# ISL.net
KiCad netlist of a schematic drawn in Altium Designer
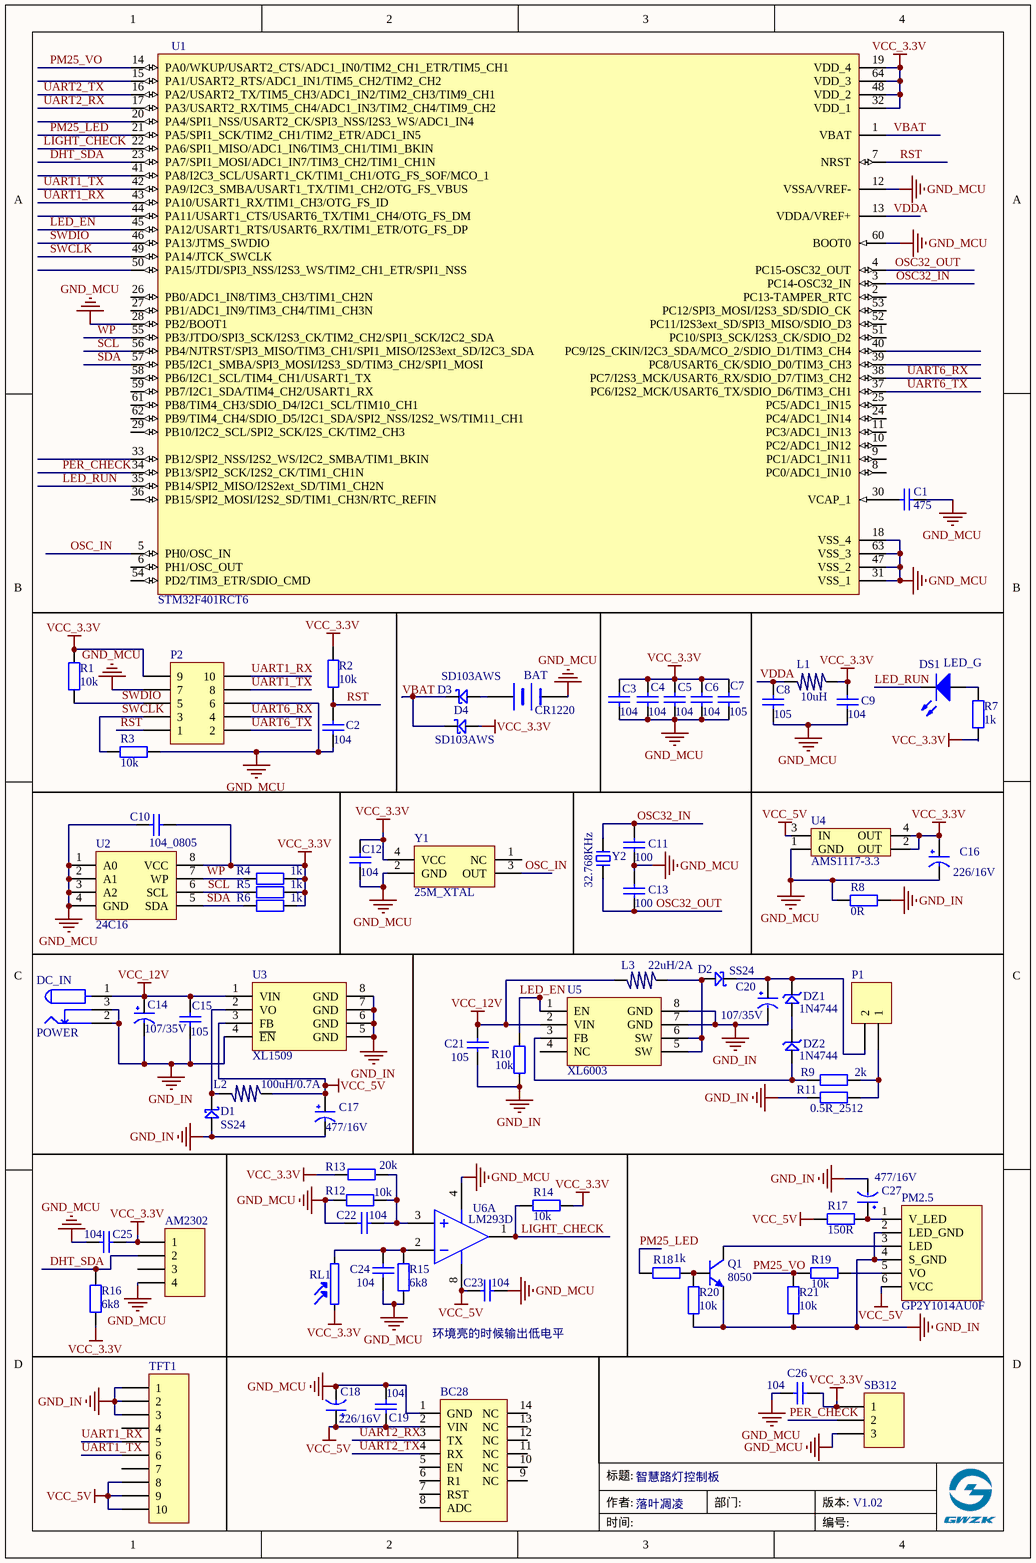
[diagram p0: ISL.SchDoc]

(export (version "E")
  (design (tool "Eeschema 10.0.6"))
  (components
    (comp (ref "AM2302")
      (value "Header 4")
      (footprint "AM2302(DHT11)")
      (description "Header, 4-Pin")
      (fields (field (name "PUBLISHER") "Altium Limited"))
      (libsource (lib "Miscellaneous Connectors") (part "Header 4"))
    )
    (comp (ref "BAT") (value "CR1220") (footprint "CR1220_B") (libsource (lib "*") (part "BATTERY")))
    (comp (ref "BC28") (value "BC28") (footprint "BC28-安联德") (libsource (lib "SCHLIB_LJF") (part "BC28")))
    (comp (ref "C1")
      (value "475")
      (footprint "C 0805")
      (description "Capacitor")
      (fields (field (name "PUBLISHER") "Altium Limited"))
      (libsource (lib "Miscellaneous Devices") (part "Cap"))
    )
    (comp (ref "C2")
      (value "104")
      (footprint "C 0805")
      (description "Capacitor")
      (fields (field (name "PUBLISHER") "Altium Limited"))
      (libsource (lib "Miscellaneous Devices") (part "Cap"))
    )
    (comp (ref "C3")
      (value "104")
      (footprint "C 0805")
      (description "Capacitor")
      (fields (field (name "PUBLISHER") "Altium Limited"))
      (libsource (lib "Miscellaneous Devices") (part "Cap"))
    )
    (comp (ref "C4")
      (value "104")
      (footprint "C 0805")
      (description "Capacitor")
      (fields (field (name "PUBLISHER") "Altium Limited"))
      (libsource (lib "Miscellaneous Devices") (part "Cap"))
    )
    (comp (ref "C5")
      (value "104")
      (footprint "C 0805")
      (description "Capacitor")
      (fields (field (name "PUBLISHER") "Altium Limited"))
      (libsource (lib "Miscellaneous Devices") (part "Cap"))
    )
    (comp (ref "C6")
      (value "104")
      (footprint "C 0805")
      (description "Capacitor")
      (fields (field (name "PUBLISHER") "Altium Limited"))
      (libsource (lib "Miscellaneous Devices") (part "Cap"))
    )
    (comp (ref "C7")
      (value "105")
      (footprint "C 0805")
      (description "Capacitor")
      (fields (field (name "PUBLISHER") "Altium Limited"))
      (libsource (lib "Miscellaneous Devices") (part "Cap"))
    )
    (comp (ref "C8")
      (value "105")
      (footprint "C 0805")
      (description "Capacitor")
      (fields (field (name "PUBLISHER") "Altium Limited"))
      (libsource (lib "Miscellaneous Devices") (part "Cap"))
    )
    (comp (ref "C9")
      (value "104")
      (footprint "C 0805")
      (description "Capacitor")
      (fields (field (name "PUBLISHER") "Altium Limited"))
      (libsource (lib "Miscellaneous Devices") (part "Cap"))
    )
    (comp (ref "C10")
      (value "104_0805")
      (footprint "C 0805")
      (description "Capacitor")
      (fields (field (name "PUBLISHER") "Altium Limited"))
      (libsource (lib "Miscellaneous Devices") (part "Cap"))
    )
    (comp (ref "C11")
      (value "100")
      (footprint "C 0805")
      (description "Capacitor")
      (fields (field (name "PUBLISHER") "Altium Limited"))
      (libsource (lib "Miscellaneous Devices") (part "Cap"))
    )
    (comp (ref "C12")
      (value "104")
      (footprint "C 0805")
      (description "Capacitor")
      (fields (field (name "PUBLISHER") "Altium Limited"))
      (libsource (lib "Miscellaneous Devices") (part "Cap"))
    )
    (comp (ref "C13")
      (value "100")
      (footprint "C 0805")
      (description "Capacitor")
      (fields (field (name "PUBLISHER") "Altium Limited"))
      (libsource (lib "Miscellaneous Devices") (part "Cap"))
    )
    (comp (ref "C14") (value "107/35V") (footprint "CAP 2.5*6.3*11.2") (libsource (lib "原理图库") (part "CAP")))
    (comp (ref "C15")
      (value "105")
      (footprint "C 0805")
      (description "Capacitor")
      (fields (field (name "PUBLISHER") "Altium Limited"))
      (libsource (lib "Miscellaneous Devices") (part "Cap"))
    )
    (comp (ref "C16") (value "226/16V") (footprint "CD B(3528)") (libsource (lib "原理图库") (part "CAP")))
    (comp (ref "C17") (value "477/16V") (footprint "CAP 3.5*8*11.5") (libsource (lib "原理图库") (part "CAP")))
    (comp (ref "C18") (value "226/16V") (footprint "CD B(3528)") (libsource (lib "") (part "CAP_1")))
    (comp (ref "C19")
      (value "104")
      (footprint "C 0805")
      (description "Capacitor")
      (fields (field (name "PUBLISHER") "Altium Limited"))
      (libsource (lib "Miscellaneous Devices") (part "Cap"))
    )
    (comp (ref "C20") (value "107/35V") (footprint "CAP 2.5*6.3*11.2") (libsource (lib "原理图库") (part "CAP")))
    (comp (ref "C21")
      (value "105")
      (footprint "C 0805")
      (description "Capacitor")
      (fields (field (name "PUBLISHER") "Altium Limited"))
      (libsource (lib "Miscellaneous Devices") (part "Cap"))
    )
    (comp (ref "C22")
      (value "104")
      (footprint "C 0805")
      (description "Capacitor")
      (fields (field (name "PUBLISHER") "Altium Limited"))
      (libsource (lib "Miscellaneous Devices") (part "Cap"))
    )
    (comp (ref "C23")
      (value "104")
      (footprint "C 0805")
      (description "Capacitor")
      (fields (field (name "PUBLISHER") "Altium Limited"))
      (libsource (lib "Miscellaneous Devices") (part "Cap"))
    )
    (comp (ref "C24")
      (value "104")
      (footprint "C 0805")
      (description "Capacitor")
      (fields (field (name "PUBLISHER") "Altium Limited"))
      (libsource (lib "Miscellaneous Devices") (part "Cap"))
    )
    (comp (ref "C25")
      (value "104")
      (footprint "C 0805")
      (description "Capacitor")
      (fields (field (name "PUBLISHER") "Altium Limited"))
      (libsource (lib "Miscellaneous Devices") (part "Cap"))
    )
    (comp (ref "C26")
      (value "104")
      (footprint "C 0805")
      (description "Capacitor")
      (fields (field (name "PUBLISHER") "Altium Limited"))
      (libsource (lib "Miscellaneous Devices") (part "Cap"))
    )
    (comp (ref "C27") (value "477/16V") (footprint "CAP 3.5*8*11.5") (libsource (lib "") (part "CAP_1")))
    (comp (ref "D1") (value "SS24") (footprint "SMA") (libsource (lib "原理图库") (part "D_SCHOTTYK")))
    (comp (ref "D2") (value "SS24") (footprint "SMA") (libsource (lib "原理图库") (part "D_SCHOTTYK")))
    (comp (ref "D3") (value "SD103AWS") (footprint "SOD-323") (libsource (lib "原理图库") (part "D_SCHOTTYK")))
    (comp (ref "D4") (value "SD103AWS") (footprint "SOD-323") (libsource (lib "原理图库") (part "D_SCHOTTYK")))
    (comp (ref "DC_IN") (value "POWER") (footprint "DC-005") (libsource (lib "原理图库") (part "POWER")))
    (comp (ref "DS1")
      (value "LED_G")
      (footprint "LED 0805")
      (description "Typical RED, GREEN, YELLOW, AMBER GaAs LED")
      (fields (field (name "PUBLISHER") "Altium Limited"))
      (libsource (lib "原理图库") (part "LED"))
    )
    (comp (ref "DZ1") (value "1N4744") (footprint "DO-41") (libsource (lib "原理图库") (part "D_ZENER")))
    (comp (ref "DZ2") (value "1N4744") (footprint "DO-41") (libsource (lib "原理图库") (part "D_ZENER")))
    (comp (ref "L1") (value "10uH") (footprint "L 0805") (libsource (lib "原理图库") (part "L")))
    (comp (ref "L2") (value "100uH/0.7A") (footprint "NR6045") (libsource (lib "原理图库") (part "L")))
    (comp (ref "L3") (value "22uH/2A") (footprint "NR6045") (libsource (lib "原理图库") (part "L")))
    (comp (ref "P1")
      (value "Header 2")
      (footprint "KF2EDGRM-X-2P")
      (description "Header, 2-Pin")
      (fields (field (name "PUBLISHER") "Altium Limited"))
      (libsource (lib "Miscellaneous Connectors") (part "Header 2"))
    )
    (comp (ref "P2")
      (value "Header 5X2")
      (footprint "HDR2.54-WI-2x5P")
      (description "Header, 5-Pin, Dual row")
      (fields (field (name "PUBLISHER") "Altium Limited"))
      (libsource (lib "Miscellaneous Connectors") (part "Header 5X2"))
    )
    (comp (ref "PM2.5")
      (value "GP2Y1014AU0F")
      (footprint "PH2.0-WS-6P")
      (libsource (lib "SCHLIB_LJF") (part "GP2Y1014AU0F"))
    )
    (comp (ref "Q1")
      (value "8050")
      (footprint "SOT23-3N")
      (description "NPN General Purpose Amplifier")
      (fields (field (name "PUBLISHER") "Altium Limited"))
      (libsource (lib "Miscellaneous Devices") (part "2N3904"))
    )
    (comp (ref "R1")
      (value "10k")
      (footprint "R 0805")
      (description "Resistor")
      (fields (field (name "PUBLISHER") "Altium Limited"))
      (libsource (lib "Miscellaneous Devices") (part "Res2"))
    )
    (comp (ref "R2")
      (value "10k")
      (footprint "R 0805")
      (description "Resistor")
      (fields (field (name "PUBLISHER") "Altium Limited"))
      (libsource (lib "Miscellaneous Devices") (part "Res2"))
    )
    (comp (ref "R3")
      (value "10k")
      (footprint "R 0805")
      (description "Resistor")
      (fields (field (name "PUBLISHER") "Altium Limited"))
      (libsource (lib "") (part "Res2_2"))
    )
    (comp (ref "R4")
      (value "1k")
      (footprint "R 0805")
      (description "Resistor")
      (fields (field (name "PUBLISHER") "Altium Limited"))
      (libsource (lib "") (part "Res2_2"))
    )
    (comp (ref "R5")
      (value "1k")
      (footprint "R 0805")
      (description "Resistor")
      (fields (field (name "PUBLISHER") "Altium Limited"))
      (libsource (lib "") (part "Res2_2"))
    )
    (comp (ref "R6")
      (value "1k")
      (footprint "R 0805")
      (description "Resistor")
      (fields (field (name "PUBLISHER") "Altium Limited"))
      (libsource (lib "") (part "Res2_2"))
    )
    (comp (ref "R7")
      (value "1k")
      (footprint "R 0805")
      (description "Resistor")
      (fields (field (name "PUBLISHER") "Altium Limited"))
      (libsource (lib "Miscellaneous Devices") (part "Res2"))
    )
    (comp (ref "R8")
      (value "0R")
      (footprint "R 0805")
      (description "Resistor")
      (fields (field (name "PUBLISHER") "Altium Limited"))
      (libsource (lib "") (part "Res2_3"))
    )
    (comp (ref "R9")
      (value "2k")
      (footprint "R 0805")
      (description "Resistor")
      (fields (field (name "PUBLISHER") "Altium Limited"))
      (libsource (lib "") (part "Res2_2"))
    )
    (comp (ref "R10")
      (value "10k")
      (footprint "R 0805")
      (description "Resistor")
      (fields (field (name "PUBLISHER") "Altium Limited"))
      (libsource (lib "") (part "Res2_1"))
    )
    (comp (ref "R11")
      (value "0.5R_2512")
      (footprint "R 2512")
      (description "Resistor")
      (fields (field (name "PUBLISHER") "Altium Limited"))
      (libsource (lib "") (part "Res2_2"))
    )
    (comp (ref "R12")
      (value "10k")
      (footprint "R 0805")
      (description "Resistor")
      (fields (field (name "PUBLISHER") "Altium Limited"))
      (libsource (lib "") (part "Res2_2"))
    )
    (comp (ref "R13")
      (value "20k")
      (footprint "R 0805")
      (description "Resistor")
      (fields (field (name "PUBLISHER") "Altium Limited"))
      (libsource (lib "") (part "Res2_3"))
    )
    (comp (ref "R14")
      (value "10k")
      (footprint "R 0805")
      (description "Resistor")
      (fields (field (name "PUBLISHER") "Altium Limited"))
      (libsource (lib "") (part "Res2_2"))
    )
    (comp (ref "R15")
      (value "6k8")
      (footprint "R 0805")
      (description "Resistor")
      (fields (field (name "PUBLISHER") "Altium Limited"))
      (libsource (lib "") (part "Res2_1"))
    )
    (comp (ref "R16")
      (value "6k8")
      (footprint "R 0805")
      (description "Resistor")
      (fields (field (name "PUBLISHER") "Altium Limited"))
      (libsource (lib "") (part "Res2_1"))
    )
    (comp (ref "R17")
      (value "150R")
      (footprint "R 0805")
      (description "Resistor")
      (fields (field (name "PUBLISHER") "Altium Limited"))
      (libsource (lib "") (part "Res2_2"))
    )
    (comp (ref "R18")
      (value "1k")
      (footprint "R 0805")
      (description "Resistor")
      (fields (field (name "PUBLISHER") "Altium Limited"))
      (libsource (lib "") (part "Res2_3"))
    )
    (comp (ref "R19")
      (value "10k")
      (footprint "R 0805")
      (description "Resistor")
      (fields (field (name "PUBLISHER") "Altium Limited"))
      (libsource (lib "") (part "Res2_2"))
    )
    (comp (ref "R20")
      (value "10k")
      (footprint "R 0805")
      (description "Resistor")
      (fields (field (name "PUBLISHER") "Altium Limited"))
      (libsource (lib "Miscellaneous Devices") (part "Res2"))
    )
    (comp (ref "R21")
      (value "10k")
      (footprint "R 0805")
      (description "Resistor")
      (fields (field (name "PUBLISHER") "Altium Limited"))
      (libsource (lib "Miscellaneous Devices") (part "Res2"))
    )
    (comp (ref "RL1") (value "RL") (footprint "光敏电阻") (libsource (lib "SCHLIB_LJF") (part "RL")))
    (comp (ref "SB312")
      (value "Header 3")
      (footprint "HDR2.54-LI-3P")
      (description "Header, 3-Pin")
      (fields (field (name "PUBLISHER") "Altium Limited"))
      (libsource (lib "Miscellaneous Connectors") (part "Header 3"))
    )
    (comp (ref "TFT1")
      (value "Header 10")
      (footprint "FPC1.0-2H-WS-10P")
      (description "Header, 10-Pin")
      (fields (field (name "PUBLISHER") "Altium Limited"))
      (libsource (lib "Miscellaneous Connectors") (part "Header 10"))
    )
    (comp (ref "U1")
      (value "STM32F401RCT6")
      (footprint "LQFP64 10x10_L")
      (libsource (lib "STM32LIB") (part "STM32F401RxT6"))
    )
    (comp (ref "U2")
      (value "24C16")
      (footprint "SOP8_L")
      (description "EEPROM")
      (libsource (lib "SCHLIB_LJF") (part "24Cxx"))
    )
    (comp (ref "U3") (value "XL1509") (footprint "SOP8_L") (libsource (lib "SCHLIB_LJF") (part "XL1059")))
    (comp (ref "U4") (value "AMS1117-3.3") (footprint "SOT223_N") (libsource (lib "原理图库") (part "AMS1117")))
    (comp (ref "U5") (value "XL6003") (footprint "SOP8_L") (libsource (lib "SCHLIB_LJF") (part "XL6003")))
    (comp (ref "U6") (value "LM293D") (footprint "SOP8_L") (libsource (lib "SCHLIB_LJF") (part "OPA_8PIN")))
    (comp (ref "Y1")
      (value "25M_XTAL")
      (footprint "OSC 7050-4P")
      (libsource (lib "SCHLIB_LJF") (part "8M_XTAL"))
    )
    (comp (ref "Y2")
      (value "32.768KHz")
      (footprint "OSC 3215-2P")
      (description "2脚晶振")
      (fields (field (name "版权归属") "源创客"))
      (libsource (lib "SCHLIB_LJF") (part "XTAL-2"))
    )
  )
  (nets
    (net (code "1") (name "/DHT_SDA") (class "Default")
      (node (ref "AM2302") (pin "2") (pinfunction "2_2") (pintype "passive"))
      (node (ref "R16") (pin "2") (pinfunction "2_2") (pintype "passive"))
      (node (ref "U1") (pin "23") (pinfunction "PA7/SPI1_MOSI/ADC1_IN7/TIM3_CH2/TIM1_CH1N_23") (pintype "bidirectional"))
    )
    (net (code "2") (name "/LED_EN") (class "Default")
      (node (ref "R10") (pin "2") (pinfunction "2_2") (pintype "passive"))
      (node (ref "U1") (pin "45") (pinfunction "PA12/USART1_RTS/USART6_RX/TIM1_ETR/OTG_FS_DP_45") (pintype "bidirectional"))
      (node (ref "U5") (pin "1") (pinfunction "EN_1") (pintype "passive"))
    )
    (net (code "3") (name "/LED_RUN") (class "Default")
      (node (ref "DS1") (pin "K") (pinfunction "K_K") (pintype "passive"))
      (node (ref "U1") (pin "35") (pinfunction "PB14/SPI2_MISO/I2S2ext_SD/TIM1_CH2N_35") (pintype "bidirectional"))
    )
    (net (code "4") (name "/LIGHT_CHECK") (class "Default")
      (node (ref "R14") (pin "1") (pinfunction "1_1") (pintype "passive"))
      (node (ref "U1") (pin "22") (pinfunction "PA6/SPI1_MISO/ADC1_IN6/TIM3_CH1/TIM1_BKIN_22") (pintype "bidirectional"))
      (node (ref "U6") (pin "1") (pinfunction "OUT_1") (pintype "passive"))
    )
    (net (code "5") (name "/OSC32_IN") (class "Default")
      (node (ref "C11") (pin "2") (pinfunction "2_2") (pintype "passive"))
      (node (ref "U1") (pin "3") (pinfunction "PC14-OSC32_IN_3") (pintype "bidirectional"))
      (node (ref "Y2") (pin "2") (pinfunction "2_2") (pintype "passive"))
    )
    (net (code "6") (name "/OSC32_OUT") (class "Default")
      (node (ref "C13") (pin "1") (pinfunction "1_1") (pintype "passive"))
      (node (ref "U1") (pin "4") (pinfunction "PC15-OSC32_OUT_4") (pintype "bidirectional"))
      (node (ref "Y2") (pin "1") (pinfunction "1_1") (pintype "passive"))
    )
    (net (code "7") (name "/OSC_IN") (class "Default")
      (node (ref "U1") (pin "5") (pinfunction "PH0/OSC_IN_5") (pintype "bidirectional"))
      (node (ref "Y1") (pin "3") (pinfunction "OUT_3") (pintype "passive"))
    )
    (net (code "8") (name "/PER_CHECK") (class "Default")
      (node (ref "SB312") (pin "2") (pinfunction "2_2") (pintype "passive"))
      (node (ref "U1") (pin "34") (pinfunction "PB13/SPI2_SCK/I2S2_CK/TIM1_CH1N_34") (pintype "bidirectional"))
    )
    (net (code "9") (name "/PM25_LED") (class "Default")
      (node (ref "R18") (pin "2") (pinfunction "2_2") (pintype "passive"))
      (node (ref "U1") (pin "21") (pinfunction "PA5/SPI1_SCK/TIM2_CH1/TIM2_ETR/ADC1_IN5_21") (pintype "bidirectional"))
    )
    (net (code "10") (name "/PM25_VO") (class "Default")
      (node (ref "R19") (pin "1") (pinfunction "1_1") (pintype "passive"))
      (node (ref "R21") (pin "1") (pinfunction "1_1") (pintype "passive"))
      (node (ref "U1") (pin "14") (pinfunction "PA0/WKUP/USART2_CTS/ADC1_IN0/TIM2_CH1_ETR/TIM5_CH1_14") (pintype "bidirectional"))
    )
    (net (code "11") (name "/RST") (class "Default")
      (node (ref "C2") (pin "2") (pinfunction "2_2") (pintype "passive"))
      (node (ref "P2") (pin "1") (pinfunction "1_1") (pintype "passive"))
      (node (ref "R2") (pin "2") (pinfunction "2_2") (pintype "passive"))
      (node (ref "U1") (pin "7") (pinfunction "NRST_7") (pintype "bidirectional"))
    )
    (net (code "12") (name "/SCL") (class "Default")
      (node (ref "R5") (pin "1") (pinfunction "1_1") (pintype "passive"))
      (node (ref "U1") (pin "56") (pinfunction "PB4/NJTRST/SPI3_MISO/TIM3_CH1/SPI1_MISO/I2S3ext_SD/I2C3_SDA_56") (pintype "bidirectional"))
      (node (ref "U2") (pin "6") (pinfunction "SCL_6") (pintype "passive"))
    )
    (net (code "13") (name "/SDA") (class "Default")
      (node (ref "R6") (pin "1") (pinfunction "1_1") (pintype "passive"))
      (node (ref "U1") (pin "57") (pinfunction "PB5/I2C1_SMBA/SPI3_MOSI/I2S3_SD/TIM3_CH2/SPI1_MOSI_57") (pintype "bidirectional"))
      (node (ref "U2") (pin "5") (pinfunction "SDA_5") (pintype "passive"))
    )
    (net (code "14") (name "/SWCLK") (class "Default")
      (node (ref "P2") (pin "3") (pinfunction "3_3") (pintype "passive"))
      (node (ref "R3") (pin "1") (pinfunction "1_1") (pintype "passive"))
      (node (ref "U1") (pin "49") (pinfunction "PA14/JTCK_SWCLK_49") (pintype "bidirectional"))
    )
    (net (code "15") (name "/SWDIO") (class "Default")
      (node (ref "P2") (pin "5") (pinfunction "5_5") (pintype "passive"))
      (node (ref "R1") (pin "2") (pinfunction "2_2") (pintype "passive"))
      (node (ref "U1") (pin "46") (pinfunction "PA13/JTMS_SWDIO_46") (pintype "bidirectional"))
    )
    (net (code "16") (name "/UART1_RX") (class "Default")
      (node (ref "P2") (pin "10") (pinfunction "10_10") (pintype "passive"))
      (node (ref "TFT1") (pin "5") (pinfunction "5_5") (pintype "passive"))
      (node (ref "U1") (pin "43") (pinfunction "PA10/USART1_RX/TIM1_CH3/OTG_FS_ID_43") (pintype "bidirectional"))
    )
    (net (code "17") (name "/UART1_TX") (class "Default")
      (node (ref "P2") (pin "8") (pinfunction "8_8") (pintype "passive"))
      (node (ref "TFT1") (pin "6") (pinfunction "6_6") (pintype "passive"))
      (node (ref "U1") (pin "42") (pinfunction "PA9/I2C3_SMBA/USART1_TX/TIM1_CH2/OTG_FS_VBUS_42") (pintype "bidirectional"))
    )
    (net (code "18") (name "/UART2_RX") (class "Default")
      (node (ref "BC28") (pin "3") (pinfunction "TX_3") (pintype "passive"))
      (node (ref "U1") (pin "17") (pinfunction "PA3/USART2_RX/TIM5_CH4/ADC1_IN3/TIM2_CH4/TIM9_CH2_17") (pintype "bidirectional"))
    )
    (net (code "19") (name "/UART2_TX") (class "Default")
      (node (ref "BC28") (pin "4") (pinfunction "RX_4") (pintype "passive"))
      (node (ref "U1") (pin "16") (pinfunction "PA2/USART2_TX/TIM5_CH3/ADC1_IN2/TIM2_CH3/TIM9_CH1_16") (pintype "bidirectional"))
    )
    (net (code "20") (name "/UART6_RX") (class "Default")
      (node (ref "P2") (pin "4") (pinfunction "4_4") (pintype "passive"))
      (node (ref "U1") (pin "38") (pinfunction "PC7/I2S3_MCK/USART6_RX/SDIO_D7/TIM3_CH2_38") (pintype "bidirectional"))
    )
    (net (code "21") (name "/UART6_TX") (class "Default")
      (node (ref "P2") (pin "2") (pinfunction "2_2") (pintype "passive"))
      (node (ref "U1") (pin "37") (pinfunction "PC6/I2S2_MCK/USART6_TX/SDIO_D6/TIM3_CH1_37") (pintype "bidirectional"))
    )
    (net (code "22") (name "/VBAT") (class "Default")
      (node (ref "D3") (pin "2") (pinfunction "K_2") (pintype "passive"))
      (node (ref "D4") (pin "2") (pinfunction "K_2") (pintype "passive"))
      (node (ref "U1") (pin "1") (pinfunction "VBAT_1") (pintype "power_in"))
    )
    (net (code "23") (name "/VDDA") (class "Default")
      (node (ref "C8") (pin "2") (pinfunction "2_2") (pintype "passive"))
      (node (ref "L1") (pin "2") (pintype "passive"))
      (node (ref "U1") (pin "13") (pinfunction "VDDA/VREF+_13") (pintype "power_in"))
    )
    (net (code "24") (name "/WP") (class "Default")
      (node (ref "R4") (pin "1") (pinfunction "1_1") (pintype "passive"))
      (node (ref "U1") (pin "55") (pinfunction "PB3/JTDO/SPI3_SCK/I2S3_CK/TIM2_CH2/SPI1_SCK/I2C2_SDA_55") (pintype "bidirectional"))
      (node (ref "U2") (pin "7") (pinfunction "WP_7") (pintype "passive"))
    )
    (net (code "25") (name "GND_IN") (class "Default")
      (node (ref "C14") (pin "2") (pinfunction "GND_2") (pintype "passive"))
      (node (ref "C15") (pin "1") (pinfunction "1_1") (pintype "passive"))
      (node (ref "C17") (pin "2") (pinfunction "GND_2") (pintype "passive"))
      (node (ref "C20") (pin "2") (pinfunction "GND_2") (pintype "passive"))
      (node (ref "C21") (pin "1") (pinfunction "1_1") (pintype "passive"))
      (node (ref "C27") (pin "2") (pinfunction "GND_2") (pintype "passive"))
      (node (ref "D1") (pin "1") (pinfunction "A_1") (pintype "passive"))
      (node (ref "DC_IN") (pin "2") (pintype "passive"))
      (node (ref "DC_IN") (pin "3") (pintype "passive"))
      (node (ref "PM2.5") (pin "2") (pinfunction "LED_GND_2") (pintype "passive"))
      (node (ref "PM2.5") (pin "4") (pinfunction "S_GND_4") (pintype "passive"))
      (node (ref "Q1") (pin "2") (pinfunction "2_2") (pintype "passive"))
      (node (ref "R10") (pin "1") (pinfunction "1_1") (pintype "passive"))
      (node (ref "R11") (pin "1") (pinfunction "1_1") (pintype "passive"))
      (node (ref "R20") (pin "2") (pinfunction "2_2") (pintype "passive"))
      (node (ref "R21") (pin "2") (pinfunction "2_2") (pintype "passive"))
      (node (ref "R8") (pin "1") (pinfunction "1_1") (pintype "passive"))
      (node (ref "TFT1") (pin "1") (pinfunction "1_1") (pintype "passive"))
      (node (ref "TFT1") (pin "2") (pinfunction "2_2") (pintype "passive"))
      (node (ref "TFT1") (pin "3") (pinfunction "3_3") (pintype "passive"))
      (node (ref "U3") (pin "4") (pinfunction "~{EN}_4") (pintype "passive"))
      (node (ref "U3") (pin "5") (pinfunction "GND_5") (pintype "passive"))
      (node (ref "U3") (pin "6") (pinfunction "GND_6") (pintype "passive"))
      (node (ref "U3") (pin "7") (pinfunction "GND_7") (pintype "passive"))
      (node (ref "U3") (pin "8") (pinfunction "GND_8") (pintype "passive"))
      (node (ref "U5") (pin "7") (pinfunction "GND_7") (pintype "passive"))
      (node (ref "U5") (pin "8") (pinfunction "GND_8") (pintype "passive"))
    )
    (net (code "26") (name "GND_MCU") (class "Default")
      (node (ref "AM2302") (pin "4") (pinfunction "4_4") (pintype "passive"))
      (node (ref "BAT") (pin "2") (pinfunction "-_2") (pintype "passive"))
      (node (ref "BC28") (pin "1") (pinfunction "GND_1") (pintype "passive"))
      (node (ref "C1") (pin "1") (pinfunction "1_1") (pintype "passive"))
      (node (ref "C10") (pin "2") (pinfunction "2_2") (pintype "passive"))
      (node (ref "C11") (pin "1") (pinfunction "1_1") (pintype "passive"))
      (node (ref "C12") (pin "1") (pinfunction "1_1") (pintype "passive"))
      (node (ref "C13") (pin "2") (pinfunction "2_2") (pintype "passive"))
      (node (ref "C16") (pin "2") (pinfunction "GND_2") (pintype "passive"))
      (node (ref "C18") (pin "2") (pinfunction "GND_2") (pintype "passive"))
      (node (ref "C19") (pin "2") (pinfunction "2_2") (pintype "passive"))
      (node (ref "C2") (pin "1") (pinfunction "1_1") (pintype "passive"))
      (node (ref "C22") (pin "2") (pinfunction "2_2") (pintype "passive"))
      (node (ref "C23") (pin "1") (pinfunction "1_1") (pintype "passive"))
      (node (ref "C24") (pin "1") (pinfunction "1_1") (pintype "passive"))
      (node (ref "C25") (pin "2") (pinfunction "2_2") (pintype "passive"))
      (node (ref "C26") (pin "2") (pinfunction "2_2") (pintype "passive"))
      (node (ref "C3") (pin "1") (pinfunction "1_1") (pintype "passive"))
      (node (ref "C4") (pin "1") (pinfunction "1_1") (pintype "passive"))
      (node (ref "C5") (pin "1") (pinfunction "1_1") (pintype "passive"))
      (node (ref "C6") (pin "1") (pinfunction "1_1") (pintype "passive"))
      (node (ref "C7") (pin "1") (pinfunction "1_1") (pintype "passive"))
      (node (ref "C8") (pin "1") (pinfunction "1_1") (pintype "passive"))
      (node (ref "C9") (pin "1") (pinfunction "1_1") (pintype "passive"))
      (node (ref "P2") (pin "6") (pinfunction "6_6") (pintype "passive"))
      (node (ref "P2") (pin "7") (pinfunction "7_7") (pintype "passive"))
      (node (ref "R12") (pin "1") (pinfunction "1_1") (pintype "passive"))
      (node (ref "R15") (pin "1") (pinfunction "1_1") (pintype "passive"))
      (node (ref "R3") (pin "2") (pinfunction "2_2") (pintype "passive"))
      (node (ref "R8") (pin "2") (pinfunction "2_2") (pintype "passive"))
      (node (ref "SB312") (pin "3") (pinfunction "3_3") (pintype "passive"))
      (node (ref "U1") (pin "12") (pinfunction "VSSA/VREF-_12") (pintype "power_in"))
      (node (ref "U1") (pin "18") (pinfunction "VSS_4_18") (pintype "power_in"))
      (node (ref "U1") (pin "28") (pinfunction "PB2/BOOT1_28") (pintype "bidirectional"))
      (node (ref "U1") (pin "31") (pinfunction "VSS_1_31") (pintype "power_in"))
      (node (ref "U1") (pin "47") (pinfunction "VSS_2_47") (pintype "power_in"))
      (node (ref "U1") (pin "60") (pinfunction "BOOT0_60") (pintype "input"))
      (node (ref "U1") (pin "63") (pinfunction "VSS_3_63") (pintype "power_in"))
      (node (ref "U2") (pin "1") (pinfunction "A0_1") (pintype "passive"))
      (node (ref "U2") (pin "2") (pinfunction "A1_2") (pintype "passive"))
      (node (ref "U2") (pin "3") (pinfunction "A2_3") (pintype "passive"))
      (node (ref "U2") (pin "4") (pinfunction "GND_4") (pintype "passive"))
      (node (ref "U4") (pin "1") (pinfunction "GND_1") (pintype "passive"))
      (node (ref "U6") (pin "4") (pinfunction "V-_4") (pintype "passive"))
      (node (ref "Y1") (pin "2") (pinfunction "GND_2") (pintype "passive"))
    )
    (net (code "27") (name "Net-(BAT-+)") (class "Default")
      (node (ref "BAT") (pin "1") (pinfunction "+_1") (pintype "passive"))
      (node (ref "D3") (pin "1") (pinfunction "A_1") (pintype "passive"))
    )
    (net (code "28") (name "Net-(C20-VCC)") (class "Default")
      (node (ref "C20") (pin "1") (pinfunction "VCC_1") (pintype "passive"))
      (node (ref "D2") (pin "2") (pinfunction "K_2") (pintype "passive"))
      (node (ref "DZ1") (pin "2") (pintype "passive"))
      (node (ref "P1") (pin "2") (pinfunction "2_2") (pintype "passive"))
    )
    (net (code "29") (name "Net-(C27-VCC)") (class "Default")
      (node (ref "C27") (pin "1") (pinfunction "VCC_1") (pintype "passive"))
      (node (ref "PM2.5") (pin "1") (pinfunction "V_LED_1") (pintype "passive"))
      (node (ref "R17") (pin "2") (pinfunction "2_2") (pintype "passive"))
    )
    (net (code "30") (name "Net-(D1-K)") (class "Default")
      (node (ref "D1") (pin "2") (pinfunction "K_2") (pintype "passive"))
      (node (ref "L2") (pin "2") (pintype "passive"))
      (node (ref "U3") (pin "2") (pinfunction "VO_2") (pintype "passive"))
    )
    (net (code "31") (name "Net-(D2-A)") (class "Default")
      (node (ref "D2") (pin "1") (pinfunction "A_1") (pintype "passive"))
      (node (ref "L3") (pin "1") (pintype "passive"))
      (node (ref "U5") (pin "5") (pinfunction "SW_5") (pintype "passive"))
      (node (ref "U5") (pin "6") (pinfunction "SW_6") (pintype "passive"))
    )
    (net (code "32") (name "Net-(DS1-PadA)") (class "Default")
      (node (ref "DS1") (pin "A") (pinfunction "A_A") (pintype "passive"))
      (node (ref "R7") (pin "1") (pinfunction "1_1") (pintype "passive"))
    )
    (net (code "33") (name "Net-(DZ1-Pad1)") (class "Default")
      (node (ref "DZ1") (pin "1") (pintype "passive"))
      (node (ref "DZ2") (pin "2") (pintype "passive"))
    )
    (net (code "34") (name "Net-(P1-Pad1)") (class "Default")
      (node (ref "P1") (pin "1") (pinfunction "1_1") (pintype "passive"))
      (node (ref "R11") (pin "2") (pinfunction "2_2") (pintype "passive"))
      (node (ref "R9") (pin "2") (pinfunction "2_2") (pintype "passive"))
    )
    (net (code "35") (name "Net-(PM2.5-LED)") (class "Default")
      (node (ref "PM2.5") (pin "3") (pinfunction "LED_3") (pintype "passive"))
      (node (ref "Q1") (pin "3") (pinfunction "3_3") (pintype "passive"))
    )
    (net (code "36") (name "Net-(PM2.5-VO)") (class "Default")
      (node (ref "PM2.5") (pin "5") (pinfunction "VO_5") (pintype "passive"))
      (node (ref "R19") (pin "2") (pinfunction "2_2") (pintype "passive"))
    )
    (net (code "37") (name "Net-(Q1-Pad1)") (class "Default")
      (node (ref "Q1") (pin "1") (pinfunction "1_1") (pintype "passive"))
      (node (ref "R18") (pin "1") (pinfunction "1_1") (pintype "passive"))
      (node (ref "R20") (pin "1") (pinfunction "1_1") (pintype "passive"))
    )
    (net (code "38") (name "Net-(U1-VCAP_1)") (class "Default")
      (node (ref "C1") (pin "2") (pinfunction "2_2") (pintype "passive"))
      (node (ref "U1") (pin "30") (pinfunction "VCAP_1_30") (pintype "input"))
    )
    (net (code "39") (name "Net-(U5-FB)") (class "Default")
      (node (ref "DZ2") (pin "1") (pintype "passive"))
      (node (ref "R9") (pin "1") (pinfunction "1_1") (pintype "passive"))
      (node (ref "U5") (pin "3") (pinfunction "FB_3") (pintype "passive"))
    )
    (net (code "40") (name "Net-(U6A-IN+)") (class "Default")
      (node (ref "C22") (pin "1") (pinfunction "1_1") (pintype "passive"))
      (node (ref "R12") (pin "2") (pinfunction "2_2") (pintype "passive"))
      (node (ref "R13") (pin "1") (pinfunction "1_1") (pintype "passive"))
      (node (ref "U6") (pin "3") (pinfunction "IN+_3") (pintype "passive"))
    )
    (net (code "41") (name "Net-(U6A-IN-)") (class "Default")
      (node (ref "C24") (pin "2") (pinfunction "2_2") (pintype "passive"))
      (node (ref "R15") (pin "2") (pinfunction "2_2") (pintype "passive"))
      (node (ref "RL1") (pin "1") (pintype "passive"))
      (node (ref "U6") (pin "2") (pinfunction "IN-_2") (pintype "passive"))
    )
    (net (code "42") (name "VCC_3.3V") (class "Default")
      (node (ref "AM2302") (pin "1") (pinfunction "1_1") (pintype "passive"))
      (node (ref "C10") (pin "1") (pinfunction "1_1") (pintype "passive"))
      (node (ref "C12") (pin "2") (pinfunction "2_2") (pintype "passive"))
      (node (ref "C16") (pin "1") (pinfunction "VCC_1") (pintype "passive"))
      (node (ref "C25") (pin "1") (pinfunction "1_1") (pintype "passive"))
      (node (ref "C26") (pin "1") (pinfunction "1_1") (pintype "passive"))
      (node (ref "C3") (pin "2") (pinfunction "2_2") (pintype "passive"))
      (node (ref "C4") (pin "2") (pinfunction "2_2") (pintype "passive"))
      (node (ref "C5") (pin "2") (pinfunction "2_2") (pintype "passive"))
      (node (ref "C6") (pin "2") (pinfunction "2_2") (pintype "passive"))
      (node (ref "C7") (pin "2") (pinfunction "2_2") (pintype "passive"))
      (node (ref "C9") (pin "2") (pinfunction "2_2") (pintype "passive"))
      (node (ref "D4") (pin "1") (pinfunction "A_1") (pintype "passive"))
      (node (ref "L1") (pin "1") (pintype "passive"))
      (node (ref "P2") (pin "9") (pinfunction "9_9") (pintype "passive"))
      (node (ref "R1") (pin "1") (pinfunction "1_1") (pintype "passive"))
      (node (ref "R13") (pin "2") (pinfunction "2_2") (pintype "passive"))
      (node (ref "R14") (pin "2") (pinfunction "2_2") (pintype "passive"))
      (node (ref "R16") (pin "1") (pinfunction "1_1") (pintype "passive"))
      (node (ref "R2") (pin "1") (pinfunction "1_1") (pintype "passive"))
      (node (ref "R4") (pin "2") (pinfunction "2_2") (pintype "passive"))
      (node (ref "R5") (pin "2") (pinfunction "2_2") (pintype "passive"))
      (node (ref "R6") (pin "2") (pinfunction "2_2") (pintype "passive"))
      (node (ref "R7") (pin "2") (pinfunction "2_2") (pintype "passive"))
      (node (ref "RL1") (pin "2") (pintype "passive"))
      (node (ref "SB312") (pin "1") (pinfunction "1_1") (pintype "passive"))
      (node (ref "U1") (pin "19") (pinfunction "VDD_4_19") (pintype "power_in"))
      (node (ref "U1") (pin "32") (pinfunction "VDD_1_32") (pintype "power_in"))
      (node (ref "U1") (pin "48") (pinfunction "VDD_2_48") (pintype "power_in"))
      (node (ref "U1") (pin "64") (pinfunction "VDD_3_64") (pintype "power_in"))
      (node (ref "U2") (pin "8") (pinfunction "VCC_8") (pintype "passive"))
      (node (ref "U4") (pin "2") (pinfunction "OUT_2") (pintype "passive"))
      (node (ref "U4") (pin "4") (pinfunction "OUT_4") (pintype "passive"))
      (node (ref "Y1") (pin "4") (pinfunction "VCC_4") (pintype "passive"))
    )
    (net (code "43") (name "VCC_5V") (class "Default")
      (node (ref "BC28") (pin "2") (pinfunction "VIN_2") (pintype "passive"))
      (node (ref "C17") (pin "1") (pinfunction "VCC_1") (pintype "passive"))
      (node (ref "C18") (pin "1") (pinfunction "VCC_1") (pintype "passive"))
      (node (ref "C19") (pin "1") (pinfunction "1_1") (pintype "passive"))
      (node (ref "C23") (pin "2") (pinfunction "2_2") (pintype "passive"))
      (node (ref "L2") (pin "1") (pintype "passive"))
      (node (ref "PM2.5") (pin "6") (pinfunction "VCC_6") (pintype "passive"))
      (node (ref "R17") (pin "1") (pinfunction "1_1") (pintype "passive"))
      (node (ref "TFT1") (pin "10") (pinfunction "10_10") (pintype "passive"))
      (node (ref "TFT1") (pin "8") (pinfunction "8_8") (pintype "passive"))
      (node (ref "TFT1") (pin "9") (pinfunction "9_9") (pintype "passive"))
      (node (ref "U3") (pin "3") (pinfunction "FB_3") (pintype "passive"))
      (node (ref "U4") (pin "3") (pinfunction "IN_3") (pintype "passive"))
      (node (ref "U6") (pin "8") (pinfunction "V+_8") (pintype "passive"))
    )
    (net (code "44") (name "VCC_12V") (class "Default")
      (node (ref "C14") (pin "1") (pinfunction "VCC_1") (pintype "passive"))
      (node (ref "C15") (pin "2") (pinfunction "2_2") (pintype "passive"))
      (node (ref "C21") (pin "2") (pinfunction "2_2") (pintype "passive"))
      (node (ref "DC_IN") (pin "1") (pintype "passive"))
      (node (ref "L3") (pin "2") (pintype "passive"))
      (node (ref "U3") (pin "1") (pinfunction "VIN_1") (pintype "passive"))
      (node (ref "U5") (pin "2") (pinfunction "VIN_2") (pintype "passive"))
    )
    (net (code "45") (name "unconnected-(AM2302-Pad3)") (class "Default")
      (node (ref "AM2302") (pin "3") (pinfunction "3_3") (pintype "passive"))
    )
    (net (code "46") (name "unconnected-(BC28-ADC-Pad8)") (class "Default")
      (node (ref "BC28") (pin "8") (pinfunction "ADC_8") (pintype "passive"))
    )
    (net (code "47") (name "unconnected-(BC28-EN-Pad5)") (class "Default")
      (node (ref "BC28") (pin "5") (pinfunction "EN_5") (pintype "passive"))
    )
    (net (code "48") (name "unconnected-(BC28-NC-Pad9)") (class "Default")
      (node (ref "BC28") (pin "9") (pinfunction "NC_9") (pintype "passive"))
    )
    (net (code "49") (name "unconnected-(BC28-NC-Pad10)") (class "Default")
      (node (ref "BC28") (pin "10") (pinfunction "NC_10") (pintype "passive"))
    )
    (net (code "50") (name "unconnected-(BC28-NC-Pad11)") (class "Default")
      (node (ref "BC28") (pin "11") (pinfunction "NC_11") (pintype "passive"))
    )
    (net (code "51") (name "unconnected-(BC28-NC-Pad12)") (class "Default")
      (node (ref "BC28") (pin "12") (pinfunction "NC_12") (pintype "passive"))
    )
    (net (code "52") (name "unconnected-(BC28-NC-Pad13)") (class "Default")
      (node (ref "BC28") (pin "13") (pinfunction "NC_13") (pintype "passive"))
    )
    (net (code "53") (name "unconnected-(BC28-NC-Pad14)") (class "Default")
      (node (ref "BC28") (pin "14") (pinfunction "NC_14") (pintype "passive"))
    )
    (net (code "54") (name "unconnected-(BC28-R1-Pad6)") (class "Default")
      (node (ref "BC28") (pin "6") (pinfunction "R1_6") (pintype "passive"))
    )
    (net (code "55") (name "unconnected-(BC28-RST-Pad7)") (class "Default")
      (node (ref "BC28") (pin "7") (pinfunction "RST_7") (pintype "passive"))
    )
    (net (code "56") (name "unconnected-(TFT1-Pad4)") (class "Default")
      (node (ref "TFT1") (pin "4") (pinfunction "4_4") (pintype "passive"))
    )
    (net (code "57") (name "unconnected-(TFT1-Pad7)") (class "Default")
      (node (ref "TFT1") (pin "7") (pinfunction "7_7") (pintype "passive"))
    )
    (net (code "58") (name "unconnected-(U1-PA1{slash}USART2_RTS{slash}ADC1_IN1{slash}TIM5_CH2{slash}TIM2_CH2-Pad15)") (class "Default")
      (node (ref "U1") (pin "15") (pinfunction "PA1/USART2_RTS/ADC1_IN1/TIM5_CH2/TIM2_CH2_15") (pintype "bidirectional"))
    )
    (net (code "59") (name "unconnected-(U1-PA4{slash}SPI1_NSS{slash}USART2_CK{slash}SPI3_NSS{slash}I2S3_WS{slash}ADC1_IN4-Pad20)") (class "Default")
      (node (ref "U1") (pin "20") (pinfunction "PA4/SPI1_NSS/USART2_CK/SPI3_NSS/I2S3_WS/ADC1_IN4_20") (pintype "bidirectional"))
    )
    (net (code "60") (name "unconnected-(U1-PA8{slash}I2C3_SCL{slash}USART1_CK{slash}TIM1_CH1{slash}OTG_FS_SOF{slash}MCO_1-Pad41)") (class "Default")
      (node (ref "U1") (pin "41") (pinfunction "PA8/I2C3_SCL/USART1_CK/TIM1_CH1/OTG_FS_SOF/MCO_1_41") (pintype "bidirectional"))
    )
    (net (code "61") (name "unconnected-(U1-PA11{slash}USART1_CTS{slash}USART6_TX{slash}TIM1_CH4{slash}OTG_FS_DM-Pad44)") (class "Default")
      (node (ref "U1") (pin "44") (pinfunction "PA11/USART1_CTS/USART6_TX/TIM1_CH4/OTG_FS_DM_44") (pintype "bidirectional"))
    )
    (net (code "62") (name "unconnected-(U1-PA15{slash}JTDI{slash}SPI3_NSS{slash}I2S3_WS{slash}TIM2_CH1_ETR{slash}SPI1_NSS-Pad50)") (class "Default")
      (node (ref "U1") (pin "50") (pinfunction "PA15/JTDI/SPI3_NSS/I2S3_WS/TIM2_CH1_ETR/SPI1_NSS_50") (pintype "bidirectional"))
    )
    (net (code "63") (name "unconnected-(U1-PB0{slash}ADC1_IN8{slash}TIM3_CH3{slash}TIM1_CH2N-Pad26)") (class "Default")
      (node (ref "U1") (pin "26") (pinfunction "PB0/ADC1_IN8/TIM3_CH3/TIM1_CH2N_26") (pintype "bidirectional"))
    )
    (net (code "64") (name "unconnected-(U1-PB1{slash}ADC1_IN9{slash}TIM3_CH4{slash}TIM1_CH3N-Pad27)") (class "Default")
      (node (ref "U1") (pin "27") (pinfunction "PB1/ADC1_IN9/TIM3_CH4/TIM1_CH3N_27") (pintype "bidirectional"))
    )
    (net (code "65") (name "unconnected-(U1-PB6{slash}I2C1_SCL{slash}TIM4_CH1{slash}USART1_TX-Pad58)") (class "Default")
      (node (ref "U1") (pin "58") (pinfunction "PB6/I2C1_SCL/TIM4_CH1/USART1_TX_58") (pintype "bidirectional"))
    )
    (net (code "66") (name "unconnected-(U1-PB7{slash}I2C1_SDA{slash}TIM4_CH2{slash}USART1_RX-Pad59)") (class "Default")
      (node (ref "U1") (pin "59") (pinfunction "PB7/I2C1_SDA/TIM4_CH2/USART1_RX_59") (pintype "bidirectional"))
    )
    (net (code "67") (name "unconnected-(U1-PB8{slash}TIM4_CH3{slash}SDIO_D4{slash}I2C1_SCL{slash}TIM10_CH1-Pad61)") (class "Default")
      (node (ref "U1") (pin "61") (pinfunction "PB8/TIM4_CH3/SDIO_D4/I2C1_SCL/TIM10_CH1_61") (pintype "bidirectional"))
    )
    (net (code "68") (name "unconnected-(U1-PB9{slash}TIM4_CH4{slash}SDIO_D5{slash}I2C1_SDA{slash}SPI2_NSS{slash}I2S2_WS{slash}TIM11_CH1-Pad62)") (class "Default")
      (node (ref "U1") (pin "62") (pinfunction "PB9/TIM4_CH4/SDIO_D5/I2C1_SDA/SPI2_NSS/I2S2_WS/TIM11_CH1_62") (pintype "bidirectional"))
    )
    (net (code "69") (name "unconnected-(U1-PB10{slash}I2C2_SCL{slash}SPI2_SCK{slash}I2S_CK{slash}TIM2_CH3-Pad29)") (class "Default")
      (node (ref "U1") (pin "29") (pinfunction "PB10/I2C2_SCL/SPI2_SCK/I2S_CK/TIM2_CH3_29") (pintype "bidirectional"))
    )
    (net (code "70") (name "unconnected-(U1-PB12{slash}SPI2_NSS{slash}I2S2_WS{slash}I2C2_SMBA{slash}TIM1_BKIN-Pad33)") (class "Default")
      (node (ref "U1") (pin "33") (pinfunction "PB12/SPI2_NSS/I2S2_WS/I2C2_SMBA/TIM1_BKIN_33") (pintype "bidirectional"))
    )
    (net (code "71") (name "unconnected-(U1-PB15{slash}SPI2_MOSI{slash}I2S2_SD{slash}TIM1_CH3N{slash}RTC_REFIN-Pad36)") (class "Default")
      (node (ref "U1") (pin "36") (pinfunction "PB15/SPI2_MOSI/I2S2_SD/TIM1_CH3N/RTC_REFIN_36") (pintype "bidirectional"))
    )
    (net (code "72") (name "unconnected-(U1-PC0{slash}ADC1_IN10-Pad8)") (class "Default")
      (node (ref "U1") (pin "8") (pinfunction "PC0/ADC1_IN10_8") (pintype "bidirectional"))
    )
    (net (code "73") (name "unconnected-(U1-PC1{slash}ADC1_IN11-Pad9)") (class "Default")
      (node (ref "U1") (pin "9") (pinfunction "PC1/ADC1_IN11_9") (pintype "bidirectional"))
    )
    (net (code "74") (name "unconnected-(U1-PC2{slash}ADC1_IN12-Pad10)") (class "Default")
      (node (ref "U1") (pin "10") (pinfunction "PC2/ADC1_IN12_10") (pintype "bidirectional"))
    )
    (net (code "75") (name "unconnected-(U1-PC3{slash}ADC1_IN13-Pad11)") (class "Default")
      (node (ref "U1") (pin "11") (pinfunction "PC3/ADC1_IN13_11") (pintype "bidirectional"))
    )
    (net (code "76") (name "unconnected-(U1-PC4{slash}ADC1_IN14-Pad24)") (class "Default")
      (node (ref "U1") (pin "24") (pinfunction "PC4/ADC1_IN14_24") (pintype "bidirectional"))
    )
    (net (code "77") (name "unconnected-(U1-PC5{slash}ADC1_IN15-Pad25)") (class "Default")
      (node (ref "U1") (pin "25") (pinfunction "PC5/ADC1_IN15_25") (pintype "bidirectional"))
    )
    (net (code "78") (name "unconnected-(U1-PC8{slash}USART6_CK{slash}SDIO_D0{slash}TIM3_CH3-Pad39)") (class "Default")
      (node (ref "U1") (pin "39") (pinfunction "PC8/USART6_CK/SDIO_D0/TIM3_CH3_39") (pintype "bidirectional"))
    )
    (net (code "79") (name "unconnected-(U1-PC9{slash}I2S_CKIN{slash}I2C3_SDA{slash}MCO_2{slash}SDIO_D1{slash}TIM3_CH4-Pad40)") (class "Default")
      (node (ref "U1") (pin "40") (pinfunction "PC9/I2S_CKIN/I2C3_SDA/MCO_2/SDIO_D1/TIM3_CH4_40") (pintype "bidirectional"))
    )
    (net (code "80") (name "unconnected-(U1-PC10{slash}SPI3_SCK{slash}I2S3_CK{slash}SDIO_D2-Pad51)") (class "Default")
      (node (ref "U1") (pin "51") (pinfunction "PC10/SPI3_SCK/I2S3_CK/SDIO_D2_51") (pintype "bidirectional"))
    )
    (net (code "81") (name "unconnected-(U1-PC11{slash}I2S3ext_SD{slash}SPI3_MISO{slash}SDIO_D3-Pad52)") (class "Default")
      (node (ref "U1") (pin "52") (pinfunction "PC11/I2S3ext_SD/SPI3_MISO/SDIO_D3_52") (pintype "bidirectional"))
    )
    (net (code "82") (name "unconnected-(U1-PC12{slash}SPI3_MOSI{slash}I2S3_SD{slash}SDIO_CK-Pad53)") (class "Default")
      (node (ref "U1") (pin "53") (pinfunction "PC12/SPI3_MOSI/I2S3_SD/SDIO_CK_53") (pintype "bidirectional"))
    )
    (net (code "83") (name "unconnected-(U1-PC13-TAMPER_RTC-Pad2)") (class "Default")
      (node (ref "U1") (pin "2") (pinfunction "PC13-TAMPER_RTC_2") (pintype "bidirectional"))
    )
    (net (code "84") (name "unconnected-(U1-PD2{slash}TIM3_ETR{slash}SDIO_CMD-Pad54)") (class "Default")
      (node (ref "U1") (pin "54") (pinfunction "PD2/TIM3_ETR/SDIO_CMD_54") (pintype "bidirectional"))
    )
    (net (code "85") (name "unconnected-(U1-PH1{slash}OSC_OUT-Pad6)") (class "Default")
      (node (ref "U1") (pin "6") (pinfunction "PH1/OSC_OUT_6") (pintype "bidirectional"))
    )
    (net (code "86") (name "unconnected-(U5-NC-Pad4)") (class "Default")
      (node (ref "U5") (pin "4") (pinfunction "NC_4") (pintype "passive"))
    )
    (net (code "87") (name "unconnected-(Y1-NC-Pad1)") (class "Default")
      (node (ref "Y1") (pin "1") (pinfunction "NC_1") (pintype "passive"))
    )
  )
)
